# MARK1_EDU_PMOD.net
KiCad netlist of a schematic drawn in Altium Designer
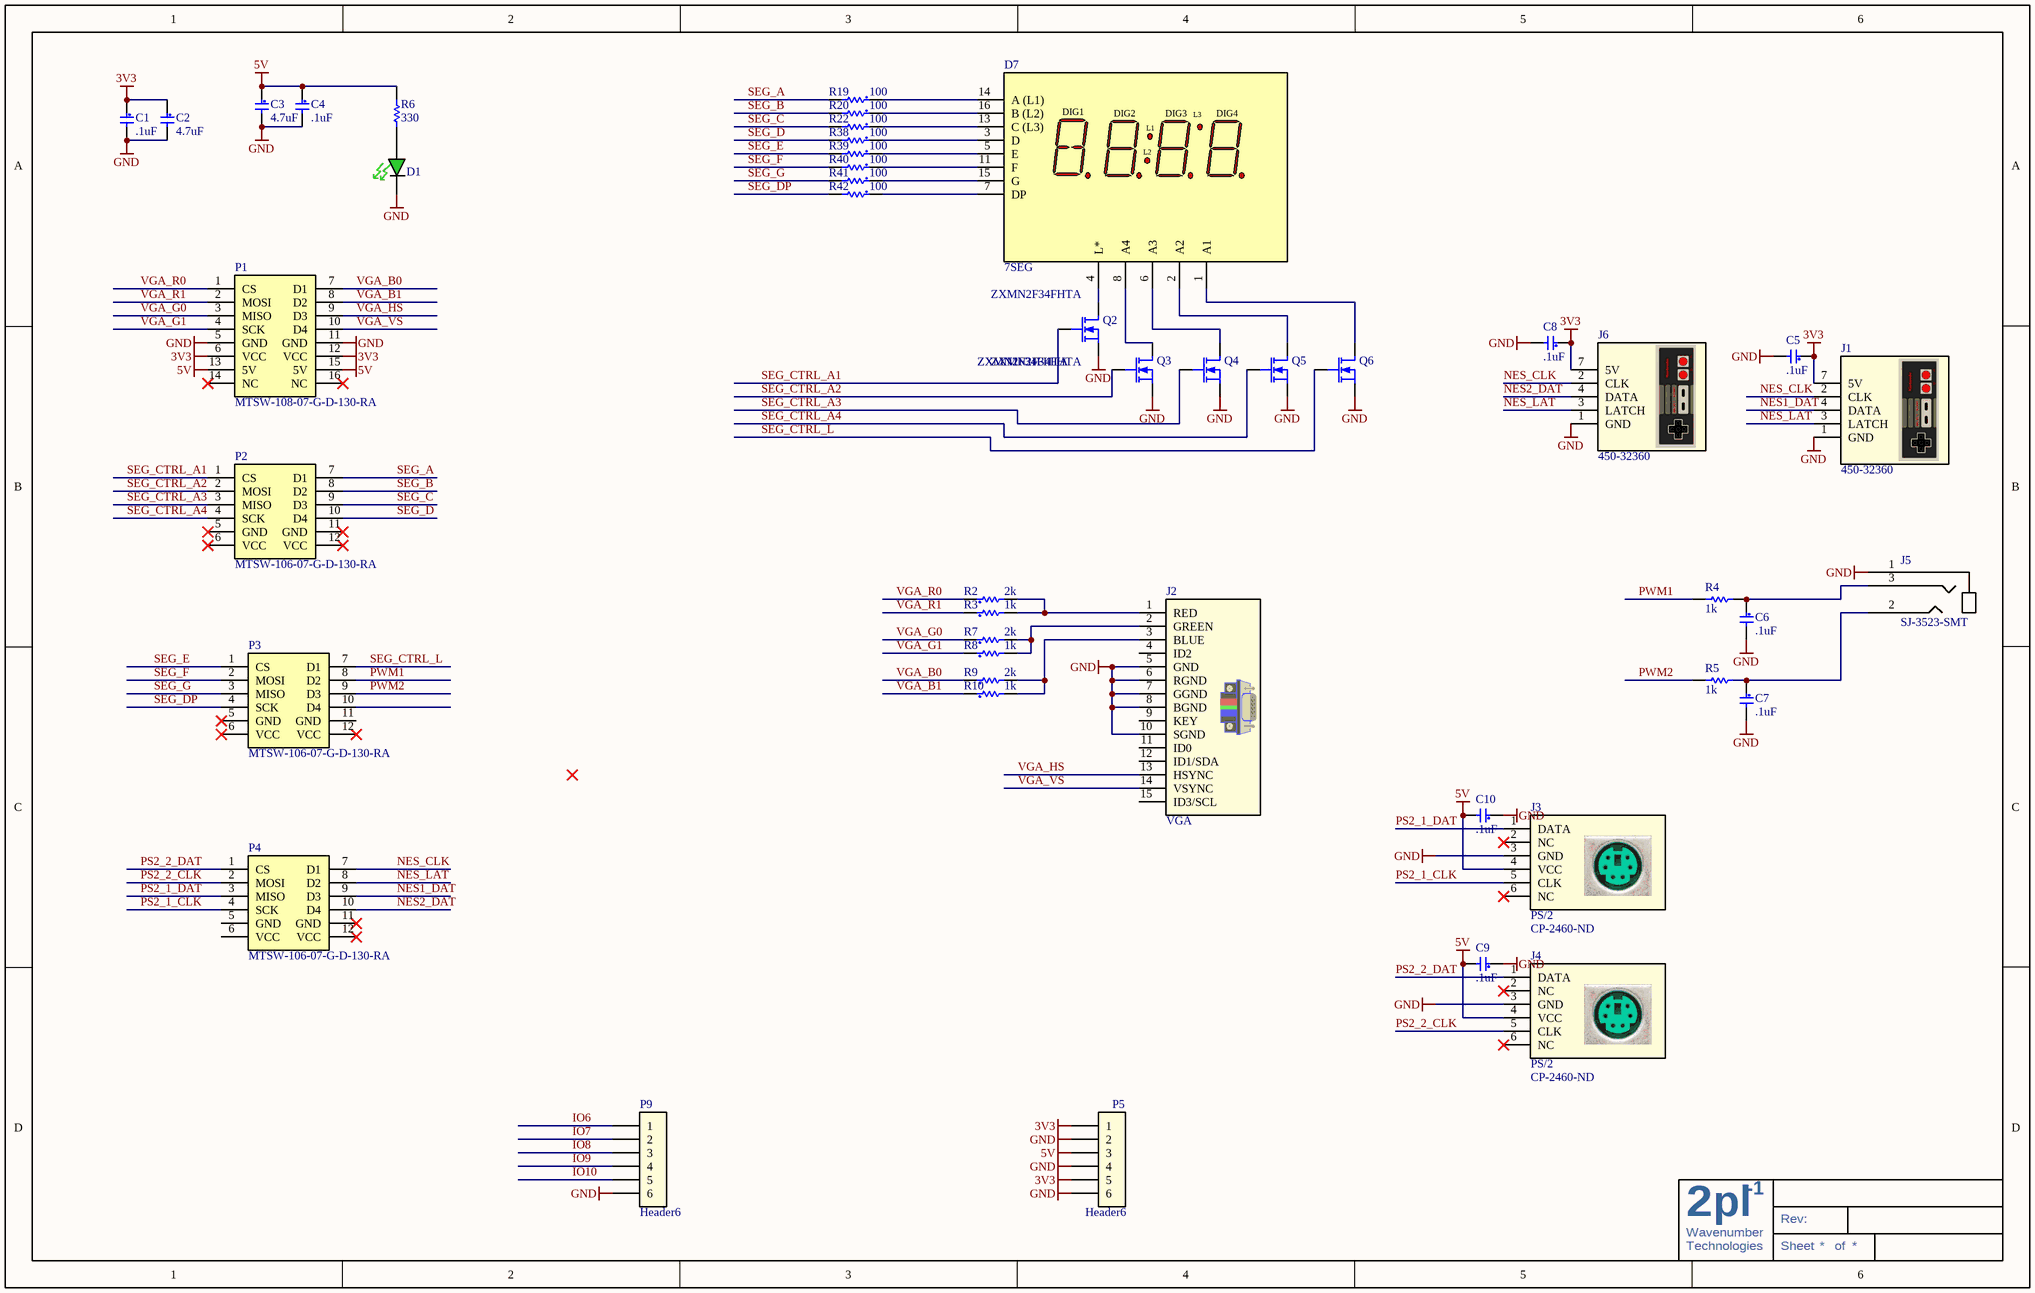
[diagram p0: MARK1_EDU_PMOD.SchDoc]

(export (version "E")
  (design (tool "Eeschema 10.0.6"))
  (components
    (comp (ref "C1")
      (value ".1uF")
      (footprint "mRCL:C0603")
      (description "0.1uF 50volts X7R 10% MLCC SMD/SMT 0603")
      (fields
        (field (name "MANUFACTURER") "Murata")
        (field (name "MANUFACTURER PART NUMBER") "GRM188R71H104KA93D")
      )
      (libsource (lib "mCapacitors") (part "C0603 - GRM188R71H104KA93D"))
    )
    (comp (ref "C2")
      (value "4.7uF")
      (footprint "mRCL:C0603")
      (description "4.7uF 10volts Y5V +80-20% (MLCC) - SMD/SMT 0603")
      (fields
        (field (name "MANUFACTURER") "Murata")
        (field (name "MANUFACTURER PART NUMBER") "GRM188F51A475ZE20D")
      )
      (libsource (lib "mCapacitors") (part "C0603 - GRM188F51A475ZE20D"))
    )
    (comp (ref "C3")
      (value "4.7uF")
      (footprint "mRCL:C0603")
      (description "4.7uF 10volts Y5V +80-20% (MLCC) - SMD/SMT 0603")
      (fields
        (field (name "MANUFACTURER") "Murata")
        (field (name "MANUFACTURER PART NUMBER") "GRM188F51A475ZE20D")
      )
      (libsource (lib "mCapacitors") (part "C0603 - GRM188F51A475ZE20D"))
    )
    (comp (ref "C4")
      (value ".1uF")
      (footprint "mRCL:C0603")
      (description "0.1uF 50volts X7R 10% MLCC SMD/SMT 0603")
      (fields
        (field (name "MANUFACTURER") "Murata")
        (field (name "MANUFACTURER PART NUMBER") "GRM188R71H104KA93D")
      )
      (libsource (lib "mCapacitors") (part "C0603 - GRM188R71H104KA93D"))
    )
    (comp (ref "C5")
      (value ".1uF")
      (footprint "mRCL:C0603")
      (description "0.1uF 50volts X7R 10% MLCC SMD/SMT 0603")
      (fields
        (field (name "MANUFACTURER") "Murata")
        (field (name "MANUFACTURER PART NUMBER") "GRM188R71H104KA93D")
      )
      (libsource (lib "mCapacitors") (part "C0603 - GRM188R71H104KA93D"))
    )
    (comp (ref "C6")
      (value ".1uF")
      (footprint "mRCL:C0603")
      (description "0.1uF 50volts X7R 10% MLCC SMD/SMT 0603")
      (fields
        (field (name "MANUFACTURER") "Murata")
        (field (name "MANUFACTURER PART NUMBER") "GRM188R71H104KA93D")
      )
      (libsource (lib "mCapacitors") (part "C0603 - GRM188R71H104KA93D"))
    )
    (comp (ref "C7")
      (value ".1uF")
      (footprint "mRCL:C0603")
      (description "0.1uF 50volts X7R 10% MLCC SMD/SMT 0603")
      (fields
        (field (name "MANUFACTURER") "Murata")
        (field (name "MANUFACTURER PART NUMBER") "GRM188R71H104KA93D")
      )
      (libsource (lib "mCapacitors") (part "C0603 - GRM188R71H104KA93D"))
    )
    (comp (ref "C8")
      (value ".1uF")
      (footprint "mRCL:C0603")
      (description "0.1uF 50volts X7R 10% MLCC SMD/SMT 0603")
      (fields
        (field (name "MANUFACTURER") "Murata")
        (field (name "MANUFACTURER PART NUMBER") "GRM188R71H104KA93D")
      )
      (libsource (lib "mCapacitors") (part "C0603 - GRM188R71H104KA93D"))
    )
    (comp (ref "C9")
      (value ".1uF")
      (footprint "mRCL:C0603")
      (description "0.1uF 50volts X7R 10% MLCC SMD/SMT 0603")
      (fields
        (field (name "MANUFACTURER") "Murata")
        (field (name "MANUFACTURER PART NUMBER") "GRM188R71H104KA93D")
      )
      (libsource (lib "mCapacitors") (part "C0603 - GRM188R71H104KA93D"))
    )
    (comp (ref "C10")
      (value ".1uF")
      (footprint "mRCL:C0603")
      (description "0.1uF 50volts X7R 10% MLCC SMD/SMT 0603")
      (fields
        (field (name "MANUFACTURER") "Murata")
        (field (name "MANUFACTURER PART NUMBER") "GRM188R71H104KA93D")
      )
      (libsource (lib "mCapacitors") (part "C0603 - GRM188R71H104KA93D"))
    )
    (comp (ref "D1")
      (value "LED 1.6X0.8MM 570NM GRN CLR SMD")
      (footprint "LED_0603 - GREEN")
      (fields
        (field (name "MANUFACTURER") "Kingbright Corp")
        (field (name "MANUFACTURER PART NUMBER") "APT1608CGCK")
      )
      (libsource (lib "eDiode") (part "APT1608CGCK"))
    )
    (comp (ref "D7")
      (value "7SEG")
      (footprint "LED - SSEG - LTC-4727JR")
      (description "LED Displays & Accessories 4 Digit, Red Low Current")
      (fields (field (name "MANUFACTURER") "Lite-On") (field (name "MANUFACTURER PART NUMBER") "LTC-4727JR"))
      (libsource (lib "eDiode") (part "LED - SSEG - LTC-4727JR"))
    )
    (comp (ref "J1")
      (value "450-32360")
      (footprint "NES - 450-32360")
      (description "NES CONTROLLER SOCKET")
      (fields (field (name "MANUFACTURER") "Parallax Inc"))
      (libsource (lib "mConnector") (part "450-32360"))
    )
    (comp (ref "J2")
      (value "VGA")
      (footprint "econnector:1-1734530-1")
      (description "CONN HD D-SUB RCPT R/A 15POS")
      (fields
        (field (name "MANUFACTURER") "TE Connectivity")
        (field (name "MANUFACTURER PART NUMBER") "1-1734530-1")
      )
      (libsource (lib "eConnector") (part "VGA - 1-1734530-1"))
    )
    (comp (ref "J3")
      (value "PS/2")
      (footprint "mconnector:MD-60S - PS/2")
      (description "CONN MINIDIN RECPT UNSHIELD 6POS - PS/2 mouse - keybaord")
      (fields
        (field (name "MANUFACTURER") "CUI Inc")
        (field (name "MANUFACTURER PART NUMBER") "MD-60S")
        (field (name "SUPPLIER PART NUMBER 1") "CP-2460-ND")
      )
      (libsource (lib "mConnector") (part "Con - D-60S"))
    )
    (comp (ref "J4")
      (value "PS/2")
      (footprint "mconnector:MD-60S - PS/2")
      (description "CONN MINIDIN RECPT UNSHIELD 6POS - PS/2 mouse - keybaord")
      (fields
        (field (name "MANUFACTURER") "CUI Inc")
        (field (name "MANUFACTURER PART NUMBER") "MD-60S")
        (field (name "SUPPLIER PART NUMBER 1") "CP-2460-ND")
      )
      (libsource (lib "mConnector") (part "Con - D-60S"))
    )
    (comp (ref "J5")
      (value "SJ-3523-SMT")
      (footprint "SJ-3523-SMT")
      (description "CONN AUDIO JACK 3.5MM STEREO SMD")
      (fields (field (name "MANUFACTURER") "CUI Inc") (field (name "SOURCE") "Digikey"))
      (libsource (lib "eConnector") (part "SJ-3523-SMT"))
    )
    (comp (ref "J6")
      (value "450-32360")
      (footprint "NES - 450-32360")
      (description "NES CONTROLLER SOCKET")
      (fields (field (name "MANUFACTURER") "Parallax Inc"))
      (libsource (lib "mConnector") (part "450-32360"))
    )
    (comp (ref "P1")
      (value "MTSW-108-07-G-D-130-RA")
      (footprint "mconnector:PMOD HEADER - MTSW-108-07-G-D-130-RA")
      (description "Conn Unshrouded Header HDR 12 POS 2.54mm Solder RA Thru-Hole")
      (fields (field (name "MANUFACTURER") "Samtec"))
      (libsource (lib "mConnector") (part "P-MOD - MTSW-108-07-G-D-130-RA"))
    )
    (comp (ref "P2")
      (value "MTSW-106-07-G-D-130-RA")
      (footprint "mconnector:PMOD HEADER - Male")
      (description "Conn Unshrouded Header HDR 12 POS 2.54mm Solder RA Thru-Hole")
      (fields (field (name "MANUFACTURER") "Samtec"))
      (libsource (lib "mConnector") (part "P-MOD - MTSW-106-07-G-D-130-RA"))
    )
    (comp (ref "P3")
      (value "MTSW-106-07-G-D-130-RA")
      (footprint "mconnector:PMOD HEADER - Male")
      (description "Conn Unshrouded Header HDR 12 POS 2.54mm Solder RA Thru-Hole")
      (fields (field (name "MANUFACTURER") "Samtec"))
      (libsource (lib "mConnector") (part "P-MOD - MTSW-106-07-G-D-130-RA"))
    )
    (comp (ref "P4")
      (value "MTSW-106-07-G-D-130-RA")
      (footprint "mconnector:PMOD HEADER - Male")
      (description "Conn Unshrouded Header HDR 12 POS 2.54mm Solder RA Thru-Hole")
      (fields (field (name "MANUFACTURER") "Samtec"))
      (libsource (lib "mConnector") (part "P-MOD - MTSW-106-07-G-D-130-RA"))
    )
    (comp (ref "P5")
      (value "Header6")
      (footprint "HEADER_6_40_100 THRU SIP")
      (description "Header 6 pin")
      (libsource (lib "mConnector") (part "Header6"))
    )
    (comp (ref "P9")
      (value "Header6")
      (footprint "HEADER_6_40_100 THRU SIP")
      (description "Header 6 pin")
      (libsource (lib "mConnector") (part "Header6"))
    )
    (comp (ref "Q2")
      (value "ZXMN2F34FHTA")
      (footprint "SOT-23")
      (description "MOSFET N-CHAN 20V SOT23-3")
      (fields (field (name "MANUFACTURER") "Diodes/Zetex"))
      (libsource (lib "eTransistor") (part "ZXMN2F34FHTA"))
    )
    (comp (ref "Q3")
      (value "ZXMN2F34FHTA")
      (footprint "SOT-23")
      (description "MOSFET N-CHAN 20V SOT23-3")
      (fields (field (name "MANUFACTURER") "Diodes/Zetex"))
      (libsource (lib "eTransistor") (part "ZXMN2F34FHTA"))
    )
    (comp (ref "Q4")
      (value "ZXMN2F34FHTA")
      (footprint "SOT-23")
      (description "MOSFET N-CHAN 20V SOT23-3")
      (fields (field (name "MANUFACTURER") "Diodes/Zetex"))
      (libsource (lib "eTransistor") (part "ZXMN2F34FHTA"))
    )
    (comp (ref "Q5")
      (value "ZXMN2F34FHTA")
      (footprint "SOT-23")
      (description "MOSFET N-CHAN 20V SOT23-3")
      (fields (field (name "MANUFACTURER") "Diodes/Zetex"))
      (libsource (lib "eTransistor") (part "ZXMN2F34FHTA"))
    )
    (comp (ref "Q6")
      (value "ZXMN2F34FHTA")
      (footprint "SOT-23")
      (description "MOSFET N-CHAN 20V SOT23-3")
      (fields (field (name "MANUFACTURER") "Diodes/Zetex"))
      (libsource (lib "eTransistor") (part "ZXMN2F34FHTA"))
    )
    (comp (ref "R2")
      (value "2k")
      (footprint "mRCL:R0603")
      (description "RES 2.00K OHM 1/10W 1% 0603 SMD")
      (fields
        (field (name "MANUFACTURER") "Panasonic - ECG")
        (field (name "MANUFACTURER PART NUMBER") "ERJ-3EKF2001V")
      )
      (libsource (lib "mResistors") (part "R0603 - ERJ-3EKF2001V"))
    )
    (comp (ref "R3")
      (value "1k")
      (footprint "mRCL:R0603")
      (description "1Kohms 1% Thick Film Resistors - SMD 0603  Tol")
      (fields
        (field (name "MANUFACTURER") "Panasonic Electronic Components")
        (field (name "MANUFACTURER PART NUMBER") "ERJ-3EKF1001V")
      )
      (libsource (lib "mResistors") (part "R0603 - ERJ-3EKF1001V"))
    )
    (comp (ref "R4")
      (value "1k")
      (footprint "R0603")
      (description "RES 1.00K OHM 1/10W 1% 0603 SMD")
      (fields
        (field (name "MANUFACTURER") "Panasonic - ECG")
        (field (name "MANUFACTURER PART NUMBER") "ERJ-3EKF1001V")
      )
      (libsource (lib "eResistors") (part "ERJ-3EKF1001V"))
    )
    (comp (ref "R5")
      (value "1k")
      (footprint "R0603")
      (description "RES 1.00K OHM 1/10W 1% 0603 SMD")
      (fields
        (field (name "MANUFACTURER") "Panasonic - ECG")
        (field (name "MANUFACTURER PART NUMBER") "ERJ-3EKF1001V")
      )
      (libsource (lib "eResistors") (part "ERJ-3EKF1001V"))
    )
    (comp (ref "R6")
      (value "330")
      (footprint "R0603")
      (description "RES 330 OHM 1/10W 1% 0603 SMD")
      (fields
        (field (name "MANUFACTURER") "Panasonic - ECG")
        (field (name "MANUFACTURER PART NUMBER") "ERJ-3EKF3300V")
      )
      (libsource (lib "eResistors") (part "ERJ-3EKF3300V"))
    )
    (comp (ref "R7")
      (value "2k")
      (footprint "mRCL:R0603")
      (description "RES 2.00K OHM 1/10W 1% 0603 SMD")
      (fields
        (field (name "MANUFACTURER") "Panasonic - ECG")
        (field (name "MANUFACTURER PART NUMBER") "ERJ-3EKF2001V")
      )
      (libsource (lib "mResistors") (part "R0603 - ERJ-3EKF2001V"))
    )
    (comp (ref "R8")
      (value "1k")
      (footprint "mRCL:R0603")
      (description "1Kohms 1% Thick Film Resistors - SMD 0603  Tol")
      (fields
        (field (name "MANUFACTURER") "Panasonic Electronic Components")
        (field (name "MANUFACTURER PART NUMBER") "ERJ-3EKF1001V")
      )
      (libsource (lib "mResistors") (part "R0603 - ERJ-3EKF1001V"))
    )
    (comp (ref "R9")
      (value "2k")
      (footprint "mRCL:R0603")
      (description "RES 2.00K OHM 1/10W 1% 0603 SMD")
      (fields
        (field (name "MANUFACTURER") "Panasonic - ECG")
        (field (name "MANUFACTURER PART NUMBER") "ERJ-3EKF2001V")
      )
      (libsource (lib "mResistors") (part "R0603 - ERJ-3EKF2001V"))
    )
    (comp (ref "R10")
      (value "1k")
      (footprint "mRCL:R0603")
      (description "1Kohms 1% Thick Film Resistors - SMD 0603  Tol")
      (fields
        (field (name "MANUFACTURER") "Panasonic Electronic Components")
        (field (name "MANUFACTURER PART NUMBER") "ERJ-3EKF1001V")
      )
      (libsource (lib "mResistors") (part "R0603 - ERJ-3EKF1001V"))
    )
    (comp (ref "R19")
      (value "100")
      (footprint "R0603")
      (description "RES 10.0K OHM 1/10W 1% 0603 SMD")
      (fields
        (field (name "MANUFACTURER") "Panasonic - ECG")
        (field (name "MANUFACTURER PART NUMBER") "ERJ-3EKF1002V")
      )
      (libsource (lib "myGeneral") (part "Res-Eli"))
    )
    (comp (ref "R20")
      (value "100")
      (footprint "R0603")
      (description "RES 10.0K OHM 1/10W 1% 0603 SMD")
      (fields
        (field (name "MANUFACTURER") "Panasonic - ECG")
        (field (name "MANUFACTURER PART NUMBER") "ERJ-3EKF1002V")
      )
      (libsource (lib "myGeneral") (part "Res-Eli"))
    )
    (comp (ref "R22")
      (value "100")
      (footprint "R0603")
      (description "RES 10.0K OHM 1/10W 1% 0603 SMD")
      (fields
        (field (name "MANUFACTURER") "Panasonic - ECG")
        (field (name "MANUFACTURER PART NUMBER") "ERJ-3EKF1002V")
      )
      (libsource (lib "myGeneral") (part "Res-Eli"))
    )
    (comp (ref "R38")
      (value "100")
      (footprint "R0603")
      (description "RES 10.0K OHM 1/10W 1% 0603 SMD")
      (fields
        (field (name "MANUFACTURER") "Panasonic - ECG")
        (field (name "MANUFACTURER PART NUMBER") "ERJ-3EKF1002V")
      )
      (libsource (lib "myGeneral") (part "Res-Eli"))
    )
    (comp (ref "R39")
      (value "100")
      (footprint "R0603")
      (description "RES 10.0K OHM 1/10W 1% 0603 SMD")
      (fields
        (field (name "MANUFACTURER") "Panasonic - ECG")
        (field (name "MANUFACTURER PART NUMBER") "ERJ-3EKF1002V")
      )
      (libsource (lib "myGeneral") (part "Res-Eli"))
    )
    (comp (ref "R40")
      (value "100")
      (footprint "R0603")
      (description "RES 10.0K OHM 1/10W 1% 0603 SMD")
      (fields
        (field (name "MANUFACTURER") "Panasonic - ECG")
        (field (name "MANUFACTURER PART NUMBER") "ERJ-3EKF1002V")
      )
      (libsource (lib "myGeneral") (part "Res-Eli"))
    )
    (comp (ref "R41")
      (value "100")
      (footprint "R0603")
      (description "RES 10.0K OHM 1/10W 1% 0603 SMD")
      (fields
        (field (name "MANUFACTURER") "Panasonic - ECG")
        (field (name "MANUFACTURER PART NUMBER") "ERJ-3EKF1002V")
      )
      (libsource (lib "myGeneral") (part "Res-Eli"))
    )
    (comp (ref "R42")
      (value "100")
      (footprint "R0603")
      (description "RES 10.0K OHM 1/10W 1% 0603 SMD")
      (fields
        (field (name "MANUFACTURER") "Panasonic - ECG")
        (field (name "MANUFACTURER PART NUMBER") "ERJ-3EKF1002V")
      )
      (libsource (lib "myGeneral") (part "Res-Eli"))
    )
  )
  (nets
    (net (code "1") (name "/IO6") (class "Default")
      (node (ref "P9") (pin "1") (pinfunction "1_1") (pintype "passive"))
    )
    (net (code "2") (name "/IO7") (class "Default")
      (node (ref "P9") (pin "2") (pinfunction "2_2") (pintype "passive"))
    )
    (net (code "3") (name "/IO8") (class "Default")
      (node (ref "P9") (pin "3") (pinfunction "3_3") (pintype "passive"))
    )
    (net (code "4") (name "/IO9") (class "Default")
      (node (ref "P9") (pin "4") (pinfunction "4_4") (pintype "passive"))
    )
    (net (code "5") (name "/IO10") (class "Default")
      (node (ref "P9") (pin "5") (pinfunction "5_5") (pintype "passive"))
    )
    (net (code "6") (name "/NES1_DAT") (class "Default")
      (node (ref "J1") (pin "4") (pinfunction "DATA_4") (pintype "passive"))
      (node (ref "P4") (pin "9") (pinfunction "D3_9") (pintype "power_in"))
    )
    (net (code "7") (name "/NES2_DAT") (class "Default")
      (node (ref "J6") (pin "4") (pinfunction "DATA_4") (pintype "passive"))
      (node (ref "P4") (pin "10") (pinfunction "D4_10") (pintype "power_in"))
    )
    (net (code "8") (name "/NES_CLK") (class "Default")
      (node (ref "J1") (pin "2") (pinfunction "CLK_2") (pintype "passive"))
      (node (ref "J6") (pin "2") (pinfunction "CLK_2") (pintype "passive"))
      (node (ref "P4") (pin "7") (pinfunction "D1_7") (pintype "power_in"))
    )
    (net (code "9") (name "/NES_LAT") (class "Default")
      (node (ref "J1") (pin "3") (pinfunction "LATCH_3") (pintype "passive"))
      (node (ref "J6") (pin "3") (pinfunction "LATCH_3") (pintype "passive"))
      (node (ref "P4") (pin "8") (pinfunction "D2_8") (pintype "power_in"))
    )
    (net (code "10") (name "/PS2_1_CLK") (class "Default")
      (node (ref "J3") (pin "5") (pinfunction "CLK_5") (pintype "passive"))
      (node (ref "P4") (pin "4") (pinfunction "SCK_4") (pintype "power_in"))
    )
    (net (code "11") (name "/PS2_1_DAT") (class "Default")
      (node (ref "J3") (pin "1") (pinfunction "DATA_1") (pintype "passive"))
      (node (ref "P4") (pin "3") (pinfunction "MISO_3") (pintype "power_in"))
    )
    (net (code "12") (name "/PS2_2_CLK") (class "Default")
      (node (ref "J4") (pin "5") (pinfunction "CLK_5") (pintype "passive"))
      (node (ref "P4") (pin "2") (pinfunction "MOSI_2") (pintype "power_in"))
    )
    (net (code "13") (name "/PS2_2_DAT") (class "Default")
      (node (ref "J4") (pin "1") (pinfunction "DATA_1") (pintype "passive"))
      (node (ref "P4") (pin "1") (pinfunction "CS_1") (pintype "power_in"))
    )
    (net (code "14") (name "/PWM1") (class "Default")
      (node (ref "P3") (pin "8") (pinfunction "D2_8") (pintype "power_in"))
      (node (ref "R4") (pin "1") (pinfunction "1_1") (pintype "passive"))
    )
    (net (code "15") (name "/PWM2") (class "Default")
      (node (ref "P3") (pin "9") (pinfunction "D3_9") (pintype "power_in"))
      (node (ref "R5") (pin "1") (pinfunction "1_1") (pintype "passive"))
    )
    (net (code "16") (name "/SEG_A") (class "Default")
      (node (ref "P2") (pin "7") (pinfunction "D1_7") (pintype "power_in"))
      (node (ref "R19") (pin "2") (pinfunction "2_2") (pintype "passive"))
    )
    (net (code "17") (name "/SEG_B") (class "Default")
      (node (ref "P2") (pin "8") (pinfunction "D2_8") (pintype "power_in"))
      (node (ref "R20") (pin "2") (pinfunction "2_2") (pintype "passive"))
    )
    (net (code "18") (name "/SEG_C") (class "Default")
      (node (ref "P2") (pin "9") (pinfunction "D3_9") (pintype "power_in"))
      (node (ref "R22") (pin "2") (pinfunction "2_2") (pintype "passive"))
    )
    (net (code "19") (name "/SEG_CTRL_A1") (class "Default")
      (node (ref "P2") (pin "1") (pinfunction "CS_1") (pintype "power_in"))
      (node (ref "Q2") (pin "1") (pinfunction "G_1") (pintype "passive"))
    )
    (net (code "20") (name "/SEG_CTRL_A2") (class "Default")
      (node (ref "P2") (pin "2") (pinfunction "MOSI_2") (pintype "power_in"))
      (node (ref "Q3") (pin "1") (pinfunction "G_1") (pintype "passive"))
    )
    (net (code "21") (name "/SEG_CTRL_A3") (class "Default")
      (node (ref "P2") (pin "3") (pinfunction "MISO_3") (pintype "power_in"))
      (node (ref "Q4") (pin "1") (pinfunction "G_1") (pintype "passive"))
    )
    (net (code "22") (name "/SEG_CTRL_A4") (class "Default")
      (node (ref "P2") (pin "4") (pinfunction "SCK_4") (pintype "power_in"))
      (node (ref "Q5") (pin "1") (pinfunction "G_1") (pintype "passive"))
    )
    (net (code "23") (name "/SEG_CTRL_L") (class "Default")
      (node (ref "P3") (pin "7") (pinfunction "D1_7") (pintype "power_in"))
      (node (ref "Q6") (pin "1") (pinfunction "G_1") (pintype "passive"))
    )
    (net (code "24") (name "/SEG_D") (class "Default")
      (node (ref "P2") (pin "10") (pinfunction "D4_10") (pintype "power_in"))
      (node (ref "R38") (pin "2") (pinfunction "2_2") (pintype "passive"))
    )
    (net (code "25") (name "/SEG_DP") (class "Default")
      (node (ref "P3") (pin "4") (pinfunction "SCK_4") (pintype "power_in"))
      (node (ref "R42") (pin "2") (pinfunction "2_2") (pintype "passive"))
    )
    (net (code "26") (name "/SEG_E") (class "Default")
      (node (ref "P3") (pin "1") (pinfunction "CS_1") (pintype "power_in"))
      (node (ref "R39") (pin "2") (pinfunction "2_2") (pintype "passive"))
    )
    (net (code "27") (name "/SEG_F") (class "Default")
      (node (ref "P3") (pin "2") (pinfunction "MOSI_2") (pintype "power_in"))
      (node (ref "R40") (pin "2") (pinfunction "2_2") (pintype "passive"))
    )
    (net (code "28") (name "/SEG_G") (class "Default")
      (node (ref "P3") (pin "3") (pinfunction "MISO_3") (pintype "power_in"))
      (node (ref "R41") (pin "2") (pinfunction "2_2") (pintype "passive"))
    )
    (net (code "29") (name "/VGA_B0") (class "Default")
      (node (ref "P1") (pin "7") (pinfunction "D1_7") (pintype "power_in"))
      (node (ref "R9") (pin "1") (pinfunction "1_1") (pintype "passive"))
    )
    (net (code "30") (name "/VGA_B1") (class "Default")
      (node (ref "P1") (pin "8") (pinfunction "D2_8") (pintype "power_in"))
      (node (ref "R10") (pin "1") (pinfunction "1_1") (pintype "passive"))
    )
    (net (code "31") (name "/VGA_G0") (class "Default")
      (node (ref "P1") (pin "3") (pinfunction "MISO_3") (pintype "power_in"))
      (node (ref "R7") (pin "1") (pinfunction "1_1") (pintype "passive"))
    )
    (net (code "32") (name "/VGA_G1") (class "Default")
      (node (ref "P1") (pin "4") (pinfunction "SCK_4") (pintype "power_in"))
      (node (ref "R8") (pin "1") (pinfunction "1_1") (pintype "passive"))
    )
    (net (code "33") (name "/VGA_HS") (class "Default")
      (node (ref "J2") (pin "13") (pinfunction "HSYNC_13") (pintype "passive"))
      (node (ref "P1") (pin "9") (pinfunction "D3_9") (pintype "power_in"))
    )
    (net (code "34") (name "/VGA_R0") (class "Default")
      (node (ref "P1") (pin "1") (pinfunction "CS_1") (pintype "power_in"))
      (node (ref "R2") (pin "1") (pinfunction "1_1") (pintype "passive"))
    )
    (net (code "35") (name "/VGA_R1") (class "Default")
      (node (ref "P1") (pin "2") (pinfunction "MOSI_2") (pintype "power_in"))
      (node (ref "R3") (pin "1") (pinfunction "1_1") (pintype "passive"))
    )
    (net (code "36") (name "/VGA_VS") (class "Default")
      (node (ref "J2") (pin "14") (pinfunction "VSYNC_14") (pintype "passive"))
      (node (ref "P1") (pin "10") (pinfunction "D4_10") (pintype "power_in"))
    )
    (net (code "37") (name "3V3") (class "Default")
      (node (ref "C1") (pin "1") (pinfunction "1_1") (pintype "passive"))
      (node (ref "C2") (pin "1") (pinfunction "1_1") (pintype "passive"))
      (node (ref "C5") (pin "1") (pinfunction "1_1") (pintype "passive"))
      (node (ref "C8") (pin "1") (pinfunction "1_1") (pintype "passive"))
      (node (ref "J1") (pin "7") (pinfunction "5V_7") (pintype "passive"))
      (node (ref "J6") (pin "7") (pinfunction "5V_7") (pintype "passive"))
      (node (ref "P1") (pin "12") (pinfunction "VCC_12") (pintype "power_in"))
      (node (ref "P1") (pin "6") (pinfunction "VCC_6") (pintype "power_in"))
      (node (ref "P5") (pin "1") (pinfunction "1_1") (pintype "passive"))
      (node (ref "P5") (pin "5") (pinfunction "5_5") (pintype "passive"))
    )
    (net (code "38") (name "5V") (class "Default")
      (node (ref "C10") (pin "2") (pinfunction "2_2") (pintype "passive"))
      (node (ref "C3") (pin "1") (pinfunction "1_1") (pintype "passive"))
      (node (ref "C4") (pin "1") (pinfunction "1_1") (pintype "passive"))
      (node (ref "C9") (pin "2") (pinfunction "2_2") (pintype "passive"))
      (node (ref "J3") (pin "4") (pinfunction "VCC_4") (pintype "passive"))
      (node (ref "J4") (pin "4") (pinfunction "VCC_4") (pintype "passive"))
      (node (ref "P1") (pin "13") (pinfunction "5V_13") (pintype "power_in"))
      (node (ref "P1") (pin "15") (pinfunction "5V_15") (pintype "power_in"))
      (node (ref "P5") (pin "3") (pinfunction "3_3") (pintype "passive"))
      (node (ref "R6") (pin "1") (pinfunction "1_1") (pintype "passive"))
    )
    (net (code "39") (name "GND") (class "Default")
      (node (ref "C1") (pin "2") (pinfunction "2_2") (pintype "passive"))
      (node (ref "C10") (pin "1") (pinfunction "1_1") (pintype "passive"))
      (node (ref "C2") (pin "2") (pinfunction "2_2") (pintype "passive"))
      (node (ref "C3") (pin "2") (pinfunction "2_2") (pintype "passive"))
      (node (ref "C4") (pin "2") (pinfunction "2_2") (pintype "passive"))
      (node (ref "C5") (pin "2") (pinfunction "2_2") (pintype "passive"))
      (node (ref "C6") (pin "2") (pinfunction "2_2") (pintype "passive"))
      (node (ref "C7") (pin "2") (pinfunction "2_2") (pintype "passive"))
      (node (ref "C8") (pin "2") (pinfunction "2_2") (pintype "passive"))
      (node (ref "C9") (pin "1") (pinfunction "1_1") (pintype "passive"))
      (node (ref "D1") (pin "C") (pinfunction "C_C") (pintype "passive"))
      (node (ref "J1") (pin "1") (pinfunction "GND_1") (pintype "passive"))
      (node (ref "J2") (pin "10") (pinfunction "SGND_10") (pintype "passive"))
      (node (ref "J2") (pin "5") (pinfunction "GND_5") (pintype "passive"))
      (node (ref "J2") (pin "6") (pinfunction "RGND_6") (pintype "passive"))
      (node (ref "J2") (pin "7") (pinfunction "GGND_7") (pintype "passive"))
      (node (ref "J2") (pin "8") (pinfunction "BGND_8") (pintype "passive"))
      (node (ref "J3") (pin "3") (pinfunction "GND_3") (pintype "passive"))
      (node (ref "J4") (pin "3") (pinfunction "GND_3") (pintype "passive"))
      (node (ref "J5") (pin "1") (pinfunction "1_1") (pintype "passive"))
      (node (ref "J6") (pin "1") (pinfunction "GND_1") (pintype "passive"))
      (node (ref "P1") (pin "11") (pinfunction "GND_11") (pintype "power_in"))
      (node (ref "P1") (pin "5") (pinfunction "GND_5") (pintype "power_in"))
      (node (ref "P5") (pin "2") (pinfunction "2_2") (pintype "passive"))
      (node (ref "P5") (pin "4") (pinfunction "4_4") (pintype "passive"))
      (node (ref "P5") (pin "6") (pinfunction "6_6") (pintype "passive"))
      (node (ref "P9") (pin "6") (pinfunction "6_6") (pintype "passive"))
      (node (ref "Q2") (pin "2") (pinfunction "2_2") (pintype "passive"))
      (node (ref "Q3") (pin "2") (pinfunction "2_2") (pintype "passive"))
      (node (ref "Q4") (pin "2") (pinfunction "2_2") (pintype "passive"))
      (node (ref "Q5") (pin "2") (pinfunction "2_2") (pintype "passive"))
      (node (ref "Q6") (pin "2") (pinfunction "2_2") (pintype "passive"))
    )
    (net (code "40") (name "Net-(C6-Pad1)") (class "Default")
      (node (ref "C6") (pin "1") (pinfunction "1_1") (pintype "passive"))
      (node (ref "J5") (pin "3") (pinfunction "3_3") (pintype "passive"))
      (node (ref "R4") (pin "2") (pinfunction "2_2") (pintype "passive"))
    )
    (net (code "41") (name "Net-(C7-Pad1)") (class "Default")
      (node (ref "C7") (pin "1") (pinfunction "1_1") (pintype "passive"))
      (node (ref "J5") (pin "2") (pinfunction "2_2") (pintype "passive"))
      (node (ref "R5") (pin "2") (pinfunction "2_2") (pintype "passive"))
    )
    (net (code "42") (name "Net-(D1-PadA)") (class "Default")
      (node (ref "D1") (pin "A") (pinfunction "A_A") (pintype "passive"))
      (node (ref "R6") (pin "2") (pinfunction "2_2") (pintype "passive"))
    )
    (net (code "43") (name "Net-(D7-A1)") (class "Default")
      (node (ref "D7") (pin "1") (pinfunction "A1_1") (pintype "passive"))
      (node (ref "Q6") (pin "3") (pinfunction "D_3") (pintype "passive"))
    )
    (net (code "44") (name "Net-(D7-A2)") (class "Default")
      (node (ref "D7") (pin "2") (pinfunction "A2_2") (pintype "passive"))
      (node (ref "Q5") (pin "3") (pinfunction "D_3") (pintype "passive"))
    )
    (net (code "45") (name "Net-(D7-A3)") (class "Default")
      (node (ref "D7") (pin "6") (pinfunction "A3_6") (pintype "passive"))
      (node (ref "Q4") (pin "3") (pinfunction "D_3") (pintype "passive"))
    )
    (net (code "46") (name "Net-(D7-A4)") (class "Default")
      (node (ref "D7") (pin "8") (pinfunction "A4_8") (pintype "passive"))
      (node (ref "Q3") (pin "3") (pinfunction "D_3") (pintype "passive"))
    )
    (net (code "47") (name "Net-(D7-A_(L1))") (class "Default")
      (node (ref "D7") (pin "14") (pinfunction "A_(L1)_14") (pintype "passive"))
      (node (ref "R19") (pin "1") (pinfunction "1_1") (pintype "passive"))
    )
    (net (code "48") (name "Net-(D7-B_(L2))") (class "Default")
      (node (ref "D7") (pin "16") (pinfunction "B_(L2)_16") (pintype "passive"))
      (node (ref "R20") (pin "1") (pinfunction "1_1") (pintype "passive"))
    )
    (net (code "49") (name "Net-(D7-C_(L3))") (class "Default")
      (node (ref "D7") (pin "13") (pinfunction "C_(L3)_13") (pintype "passive"))
      (node (ref "R22") (pin "1") (pinfunction "1_1") (pintype "passive"))
    )
    (net (code "50") (name "Net-(D7-D)") (class "Default")
      (node (ref "D7") (pin "3") (pinfunction "D_3") (pintype "passive"))
      (node (ref "R38") (pin "1") (pinfunction "1_1") (pintype "passive"))
    )
    (net (code "51") (name "Net-(D7-DP)") (class "Default")
      (node (ref "D7") (pin "7") (pinfunction "DP_7") (pintype "passive"))
      (node (ref "R42") (pin "1") (pinfunction "1_1") (pintype "passive"))
    )
    (net (code "52") (name "Net-(D7-E)") (class "Default")
      (node (ref "D7") (pin "5") (pinfunction "E_5") (pintype "passive"))
      (node (ref "R39") (pin "1") (pinfunction "1_1") (pintype "passive"))
    )
    (net (code "53") (name "Net-(D7-F)") (class "Default")
      (node (ref "D7") (pin "11") (pinfunction "F_11") (pintype "passive"))
      (node (ref "R40") (pin "1") (pinfunction "1_1") (pintype "passive"))
    )
    (net (code "54") (name "Net-(D7-G)") (class "Default")
      (node (ref "D7") (pin "15") (pinfunction "G_15") (pintype "passive"))
      (node (ref "R41") (pin "1") (pinfunction "1_1") (pintype "passive"))
    )
    (net (code "55") (name "Net-(D7-L*)") (class "Default")
      (node (ref "D7") (pin "4") (pinfunction "L*_4") (pintype "passive"))
      (node (ref "Q2") (pin "3") (pinfunction "D_3") (pintype "passive"))
    )
    (net (code "56") (name "Net-(J2-BLUE)") (class "Default")
      (node (ref "J2") (pin "3") (pinfunction "BLUE_3") (pintype "passive"))
      (node (ref "R10") (pin "2") (pinfunction "2_2") (pintype "passive"))
      (node (ref "R9") (pin "2") (pinfunction "2_2") (pintype "passive"))
    )
    (net (code "57") (name "Net-(J2-GREEN)") (class "Default")
      (node (ref "J2") (pin "2") (pinfunction "GREEN_2") (pintype "passive"))
      (node (ref "R7") (pin "2") (pinfunction "2_2") (pintype "passive"))
      (node (ref "R8") (pin "2") (pinfunction "2_2") (pintype "passive"))
    )
    (net (code "58") (name "Net-(J2-RED)") (class "Default")
      (node (ref "J2") (pin "1") (pinfunction "RED_1") (pintype "passive"))
      (node (ref "R2") (pin "2") (pinfunction "2_2") (pintype "passive"))
      (node (ref "R3") (pin "2") (pinfunction "2_2") (pintype "passive"))
    )
    (net (code "59") (name "unconnected-(J2-ID0-Pad11)") (class "Default")
      (node (ref "J2") (pin "11") (pinfunction "ID0_11") (pintype "passive"))
    )
    (net (code "60") (name "unconnected-(J2-ID1{slash}SDA-Pad12)") (class "Default")
      (node (ref "J2") (pin "12") (pinfunction "ID1/SDA_12") (pintype "passive"))
    )
    (net (code "61") (name "unconnected-(J2-ID2-Pad4)") (class "Default")
      (node (ref "J2") (pin "4") (pinfunction "ID2_4") (pintype "passive"))
    )
    (net (code "62") (name "unconnected-(J2-ID3{slash}SCL-Pad15)") (class "Default")
      (node (ref "J2") (pin "15") (pinfunction "ID3/SCL_15") (pintype "passive"))
    )
    (net (code "63") (name "unconnected-(J2-KEY-Pad9)") (class "Default")
      (node (ref "J2") (pin "9") (pinfunction "KEY_9") (pintype "passive"))
    )
    (net (code "64") (name "unconnected-(J3-NC-Pad2)") (class "Default")
      (node (ref "J3") (pin "2") (pinfunction "NC_2") (pintype "passive+no_connect"))
    )
    (net (code "65") (name "unconnected-(J3-NC-Pad6)") (class "Default")
      (node (ref "J3") (pin "6") (pinfunction "NC_6") (pintype "passive+no_connect"))
    )
    (net (code "66") (name "unconnected-(J4-NC-Pad2)") (class "Default")
      (node (ref "J4") (pin "2") (pinfunction "NC_2") (pintype "passive+no_connect"))
    )
    (net (code "67") (name "unconnected-(J4-NC-Pad6)") (class "Default")
      (node (ref "J4") (pin "6") (pinfunction "NC_6") (pintype "passive+no_connect"))
    )
    (net (code "68") (name "unconnected-(P1-NC-Pad14)") (class "Default")
      (node (ref "P1") (pin "14") (pinfunction "NC_14") (pintype "power_in+no_connect"))
    )
    (net (code "69") (name "unconnected-(P1-NC-Pad16)") (class "Default")
      (node (ref "P1") (pin "16") (pinfunction "NC_16") (pintype "power_in+no_connect"))
    )
    (net (code "70") (name "unconnected-(P2-GND-Pad5)") (class "Default")
      (node (ref "P2") (pin "5") (pinfunction "GND_5") (pintype "power_in+no_connect"))
    )
    (net (code "71") (name "unconnected-(P2-GND-Pad11)") (class "Default")
      (node (ref "P2") (pin "11") (pinfunction "GND_11") (pintype "power_in+no_connect"))
    )
    (net (code "72") (name "unconnected-(P2-VCC-Pad6)") (class "Default")
      (node (ref "P2") (pin "6") (pinfunction "VCC_6") (pintype "power_in+no_connect"))
    )
    (net (code "73") (name "unconnected-(P2-VCC-Pad12)") (class "Default")
      (node (ref "P2") (pin "12") (pinfunction "VCC_12") (pintype "power_in+no_connect"))
    )
    (net (code "74") (name "unconnected-(P3-D4-Pad10)") (class "Default")
      (node (ref "P3") (pin "10") (pinfunction "D4_10") (pintype "power_in"))
    )
    (net (code "75") (name "unconnected-(P3-GND-Pad5)") (class "Default")
      (node (ref "P3") (pin "5") (pinfunction "GND_5") (pintype "power_in+no_connect"))
    )
    (net (code "76") (name "unconnected-(P3-GND-Pad11)") (class "Default")
      (node (ref "P3") (pin "11") (pinfunction "GND_11") (pintype "power_in"))
    )
    (net (code "77") (name "unconnected-(P3-VCC-Pad6)") (class "Default")
      (node (ref "P3") (pin "6") (pinfunction "VCC_6") (pintype "power_in+no_connect"))
    )
    (net (code "78") (name "unconnected-(P3-VCC-Pad12)") (class "Default")
      (node (ref "P3") (pin "12") (pinfunction "VCC_12") (pintype "power_in+no_connect"))
    )
    (net (code "79") (name "unconnected-(P4-GND-Pad5)") (class "Default")
      (node (ref "P4") (pin "5") (pinfunction "GND_5") (pintype "power_in"))
    )
    (net (code "80") (name "unconnected-(P4-GND-Pad11)") (class "Default")
      (node (ref "P4") (pin "11") (pinfunction "GND_11") (pintype "power_in+no_connect"))
    )
    (net (code "81") (name "unconnected-(P4-VCC-Pad6)") (class "Default")
      (node (ref "P4") (pin "6") (pinfunction "VCC_6") (pintype "power_in"))
    )
    (net (code "82") (name "unconnected-(P4-VCC-Pad12)") (class "Default")
      (node (ref "P4") (pin "12") (pinfunction "VCC_12") (pintype "power_in+no_connect"))
    )
  )
)
